# and.net
KiCad netlist of a schematic drawn in EAGLE
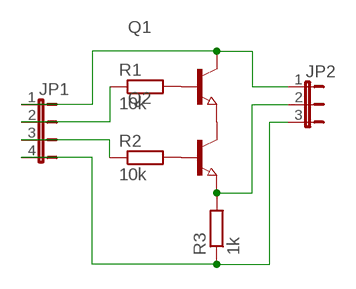
[diagram p0: schematic, sheet 1]

(export (version "E")
  (design (tool "Eeschema 10.0.6"))
  (components
    (comp (ref "JP1")
      (value "JP4E")
      (footprint "eagle-import:JP4")
      (libsource (lib "eagle-import") (part "JP4E"))
    )
    (comp (ref "JP2")
      (value "JP2W")
      (footprint "eagle-import:JP2W")
      (libsource (lib "eagle-import") (part "JP2W"))
    )
    (comp (ref "Q1")
      (value "NPN-TRANSISTOR_SOT23")
      (footprint "eagle-import:SOT23")
      (libsource (lib "eagle-import") (part "NPN-TRANSISTOR_SOT23"))
    )
    (comp (ref "Q2")
      (value "NPN-TRANSISTOR_SOT23")
      (footprint "eagle-import:SOT23")
      (libsource (lib "eagle-import") (part "NPN-TRANSISTOR_SOT23"))
    )
    (comp (ref "R1")
      (value "10k")
      (footprint "eagle-import:R1206")
      (libsource (lib "eagle-import") (part "R-EU_R1206"))
    )
    (comp (ref "R2")
      (value "10k")
      (footprint "eagle-import:R1206")
      (libsource (lib "eagle-import") (part "R-EU_R1206"))
    )
    (comp (ref "R3")
      (value "1k")
      (footprint "eagle-import:R1206")
      (libsource (lib "eagle-import") (part "R-EU_R1206"))
    )
  )
  (nets
    (net (code "1") (name "Net-(JP1-Pad2)") (class "Default")
      (node (ref "JP1") (pin "2") (pinfunction "2_2") (pintype "passive"))
      (node (ref "R1") (pin "1") (pinfunction "1_1") (pintype "passive"))
    )
    (net (code "2") (name "Net-(JP1-Pad3)") (class "Default")
      (node (ref "JP1") (pin "3") (pinfunction "3_3") (pintype "passive"))
      (node (ref "R2") (pin "1") (pinfunction "1_1") (pintype "passive"))
    )
    (net (code "3") (name "Net-(JP1-Pad4)") (class "Default")
      (node (ref "JP1") (pin "4") (pinfunction "4_4") (pintype "passive"))
      (node (ref "JP2") (pin "3") (pinfunction "3_3") (pintype "passive"))
      (node (ref "R3") (pin "1") (pinfunction "1_1") (pintype "passive"))
    )
    (net (code "4") (name "Net-(Q1-B)") (class "Default")
      (node (ref "Q1") (pin "1") (pinfunction "B_1") (pintype "passive"))
      (node (ref "R1") (pin "2") (pinfunction "2_2") (pintype "passive"))
    )
    (net (code "5") (name "Net-(Q1-C)") (class "Default")
      (node (ref "JP1") (pin "1") (pinfunction "1_1") (pintype "passive"))
      (node (ref "JP2") (pin "1") (pinfunction "1_1") (pintype "passive"))
      (node (ref "Q1") (pin "3") (pinfunction "C_3") (pintype "passive"))
    )
    (net (code "6") (name "Net-(Q1-E)") (class "Default")
      (node (ref "Q1") (pin "2") (pinfunction "E_2") (pintype "passive"))
      (node (ref "Q2") (pin "3") (pinfunction "C_3") (pintype "passive"))
    )
    (net (code "7") (name "Net-(Q2-B)") (class "Default")
      (node (ref "Q2") (pin "1") (pinfunction "B_1") (pintype "passive"))
      (node (ref "R2") (pin "2") (pinfunction "2_2") (pintype "passive"))
    )
    (net (code "8") (name "Net-(Q2-E)") (class "Default")
      (node (ref "JP2") (pin "2") (pinfunction "2_2") (pintype "passive"))
      (node (ref "Q2") (pin "2") (pinfunction "E_2") (pintype "passive"))
      (node (ref "R3") (pin "2") (pinfunction "2_2") (pintype "passive"))
    )
  )
)
